# SCH_PCB_-_project_2022-06-17.net
KiCad netlist of a schematic drawn in EasyEDA
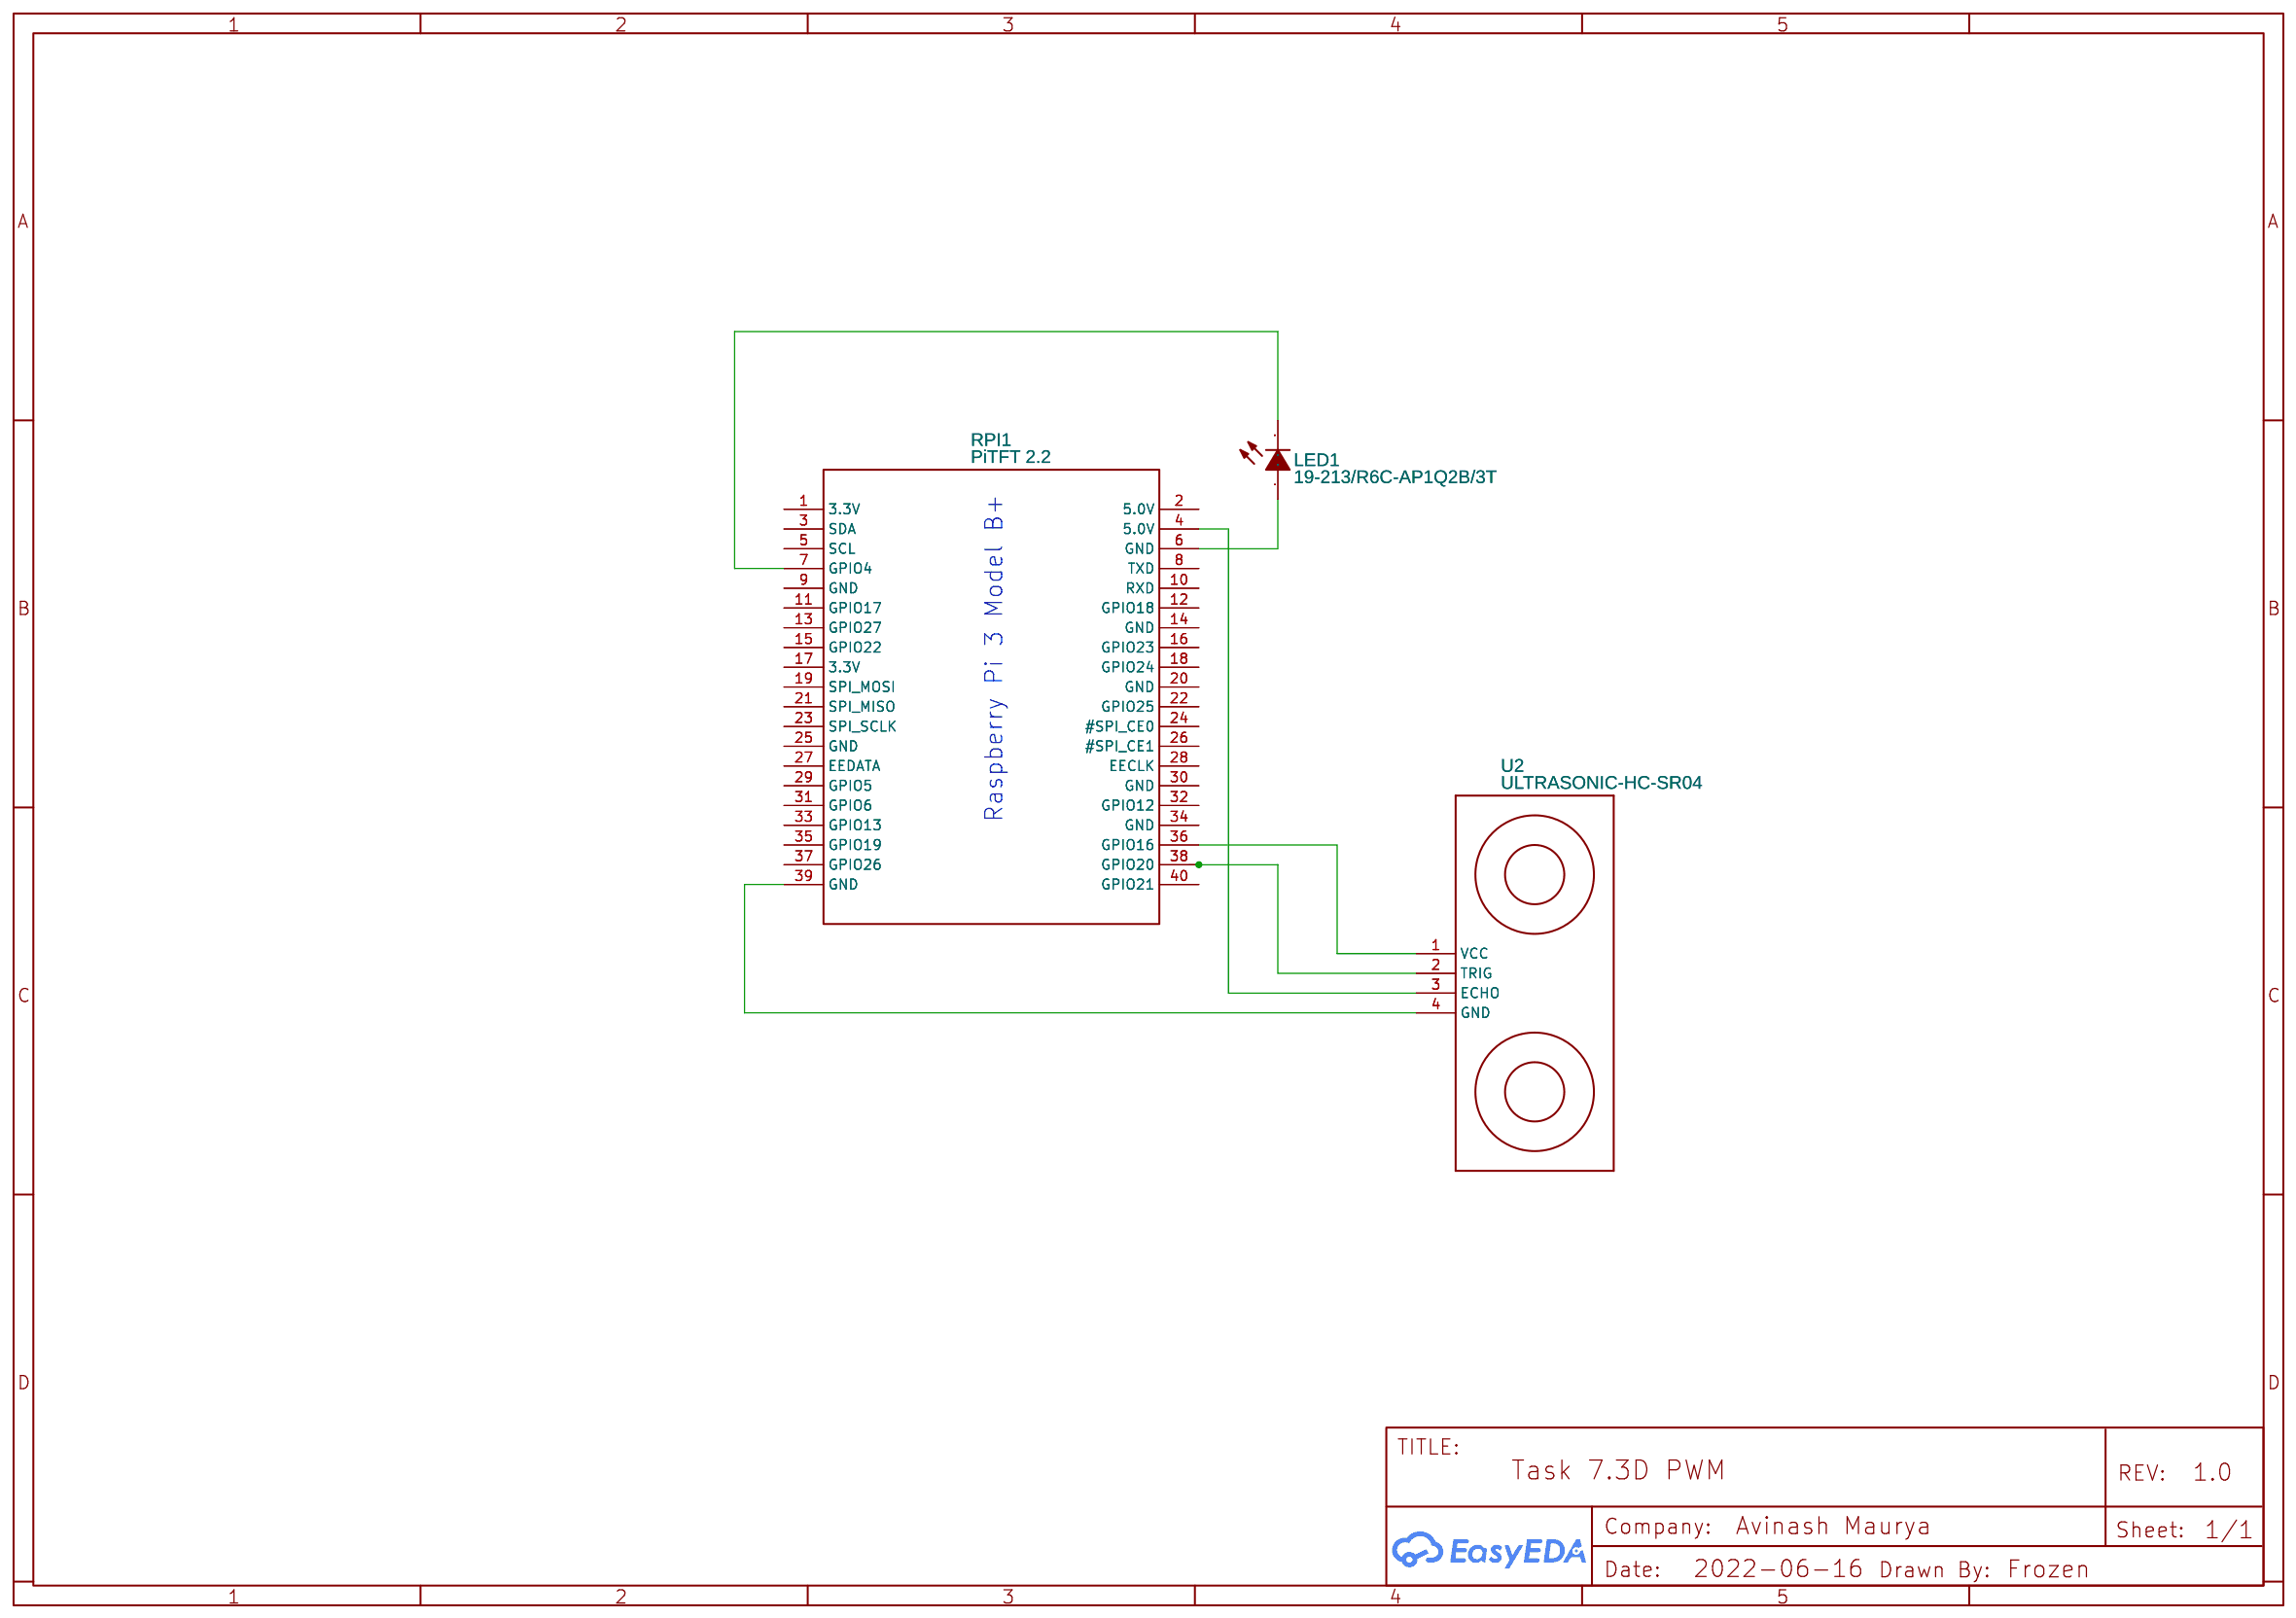
[diagram p0: Sheet_1]
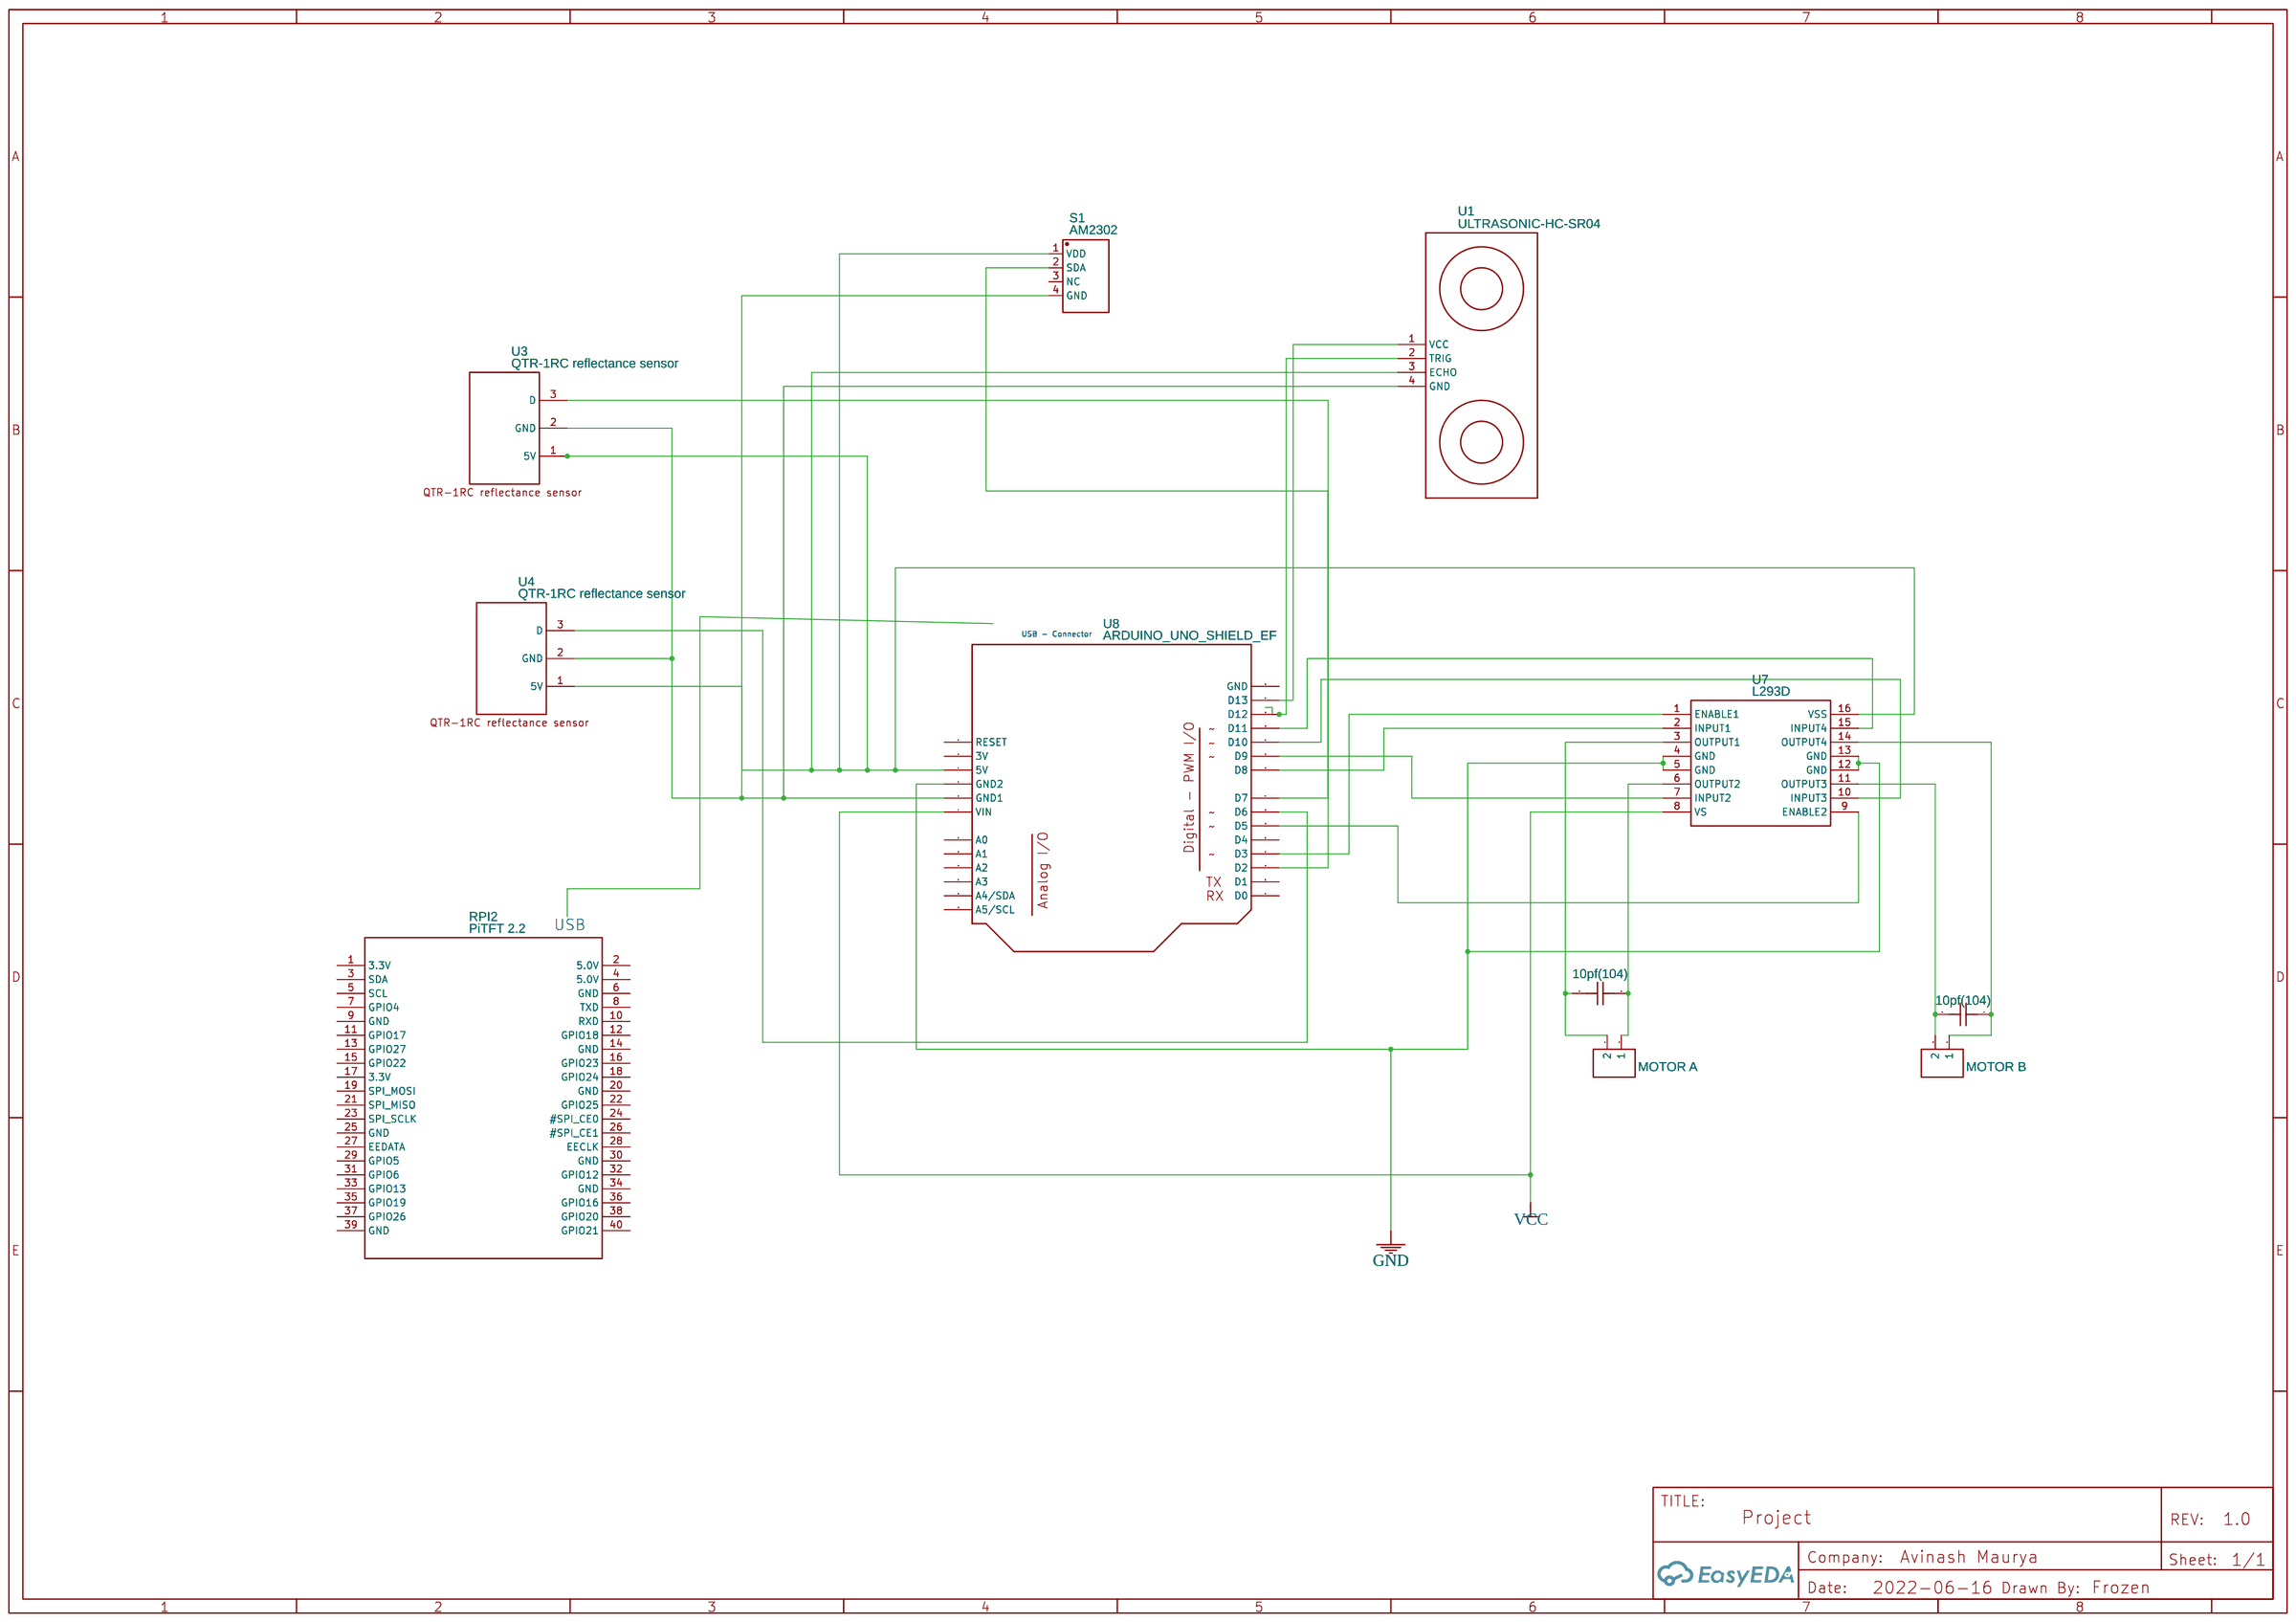
[diagram p1: Sheet_2]

(export (version "E")
  (design (tool "Eeschema 10.0.6"))
  (components
    (comp (ref "LED1")
      (value "19-213/R6C-AP1Q2B/3T")
      (fields (field (name "BOM_Supplier Part") "C212335"))
      (libsource (lib "") (part "19-213/R6C-AP1Q2B/3T"))
    )
    (comp (ref "RPI1") (value "PiTFT 2.2") (libsource (lib "") (part "PiTFT 2.2")))
    (comp (ref "U2") (value "ULTRASONIC-HC-SR04") (libsource (lib "") (part "ULTRASONIC-HC-SR04")))
    (comp (ref "C1") (value "10pf(104)") (libsource (lib "") (part "Cap_RAD-0.1_US")))
    (comp (ref "C2") (value "10pf(104)") (libsource (lib "") (part "Cap_RAD-0.1_US_1")))
    (comp (ref "P2")
      (value "MOTOR A")
      (fields
        (field (name "BOM_Manufacturer Part") "2.54-1*2PFemale")
        (field (name "BOM_Supplier Part") "C49661")
      )
      (libsource (lib "") (part "Unknown_1870_1395"))
    )
    (comp (ref "P3")
      (value "MOTOR B")
      (fields
        (field (name "BOM_Manufacturer Part") "2.54-1*2PFemale")
        (field (name "BOM_Supplier Part") "C49661")
      )
      (libsource (lib "") (part "Unknown_2105_1395"))
    )
    (comp (ref "RPI2") (value "PiTFT 2.2") (libsource (lib "") (part "PiTFT 2.2")))
    (comp (ref "S1")
      (value "AM2302")
      (fields (field (name "BOM_Supplier Part") "C83988"))
      (libsource (lib "") (part "AM2302"))
    )
    (comp (ref "U1") (value "ULTRASONIC-HC-SR04") (libsource (lib "") (part "ULTRASONIC-HC-SR04")))
    (comp (ref "U3")
      (value "QTR-1RC reflectance sensor")
      (libsource (lib "") (part "QTR-1RC reflectance sensor"))
    )
    (comp (ref "U4")
      (value "QTR-1RC reflectance sensor")
      (libsource (lib "") (part "QTR-1RC reflectance sensor"))
    )
    (comp (ref "U7")
      (value "L293D")
      (fields (field (name "BOM_Supplier Part") "C12340"))
      (libsource (lib "") (part "Unknown_1975_1190"))
    )
    (comp (ref "U8")
      (value "ARDUINO_UNO_SHIELD_EF")
      (fields (field (name "BOM_Manufacturer Part") "Arduino_UNO_R3_Shield"))
      (libsource (lib "") (part "Unknown_1510_1190"))
    )
  )
  (nets
    (net (code "1") (name "GND") (class "Default")
      (node (ref "U7") (pin "12") (pinfunction "GND_12") (pintype "unspecified"))
      (node (ref "U7") (pin "13") (pinfunction "GND_13") (pintype "unspecified"))
      (node (ref "U7") (pin "4") (pinfunction "GND_4") (pintype "unspecified"))
      (node (ref "U7") (pin "5") (pinfunction "GND_5") (pintype "unspecified"))
      (node (ref "U8") (pin "5") (pinfunction "GND2_5") (pintype "passive"))
    )
    (net (code "2") (name "Net-(LED1-A)") (class "Default")
      (node (ref "LED1") (pin "1") (pinfunction "A_1") (pintype "input"))
      (node (ref "RPI1") (pin "6") (pinfunction "GND_6") (pintype "unspecified"))
    )
    (net (code "3") (name "Net-(LED1-C)") (class "Default")
      (node (ref "LED1") (pin "2") (pinfunction "C_2") (pintype "input"))
      (node (ref "RPI1") (pin "7") (pinfunction "GPIO4_7") (pintype "unspecified"))
    )
    (net (code "4") (name "Net-(RPI1-GPIO16)") (class "Default")
      (node (ref "RPI1") (pin "36") (pinfunction "GPIO16_36") (pintype "unspecified"))
      (node (ref "U2") (pin "1") (pinfunction "VCC_1") (pintype "passive"))
    )
    (net (code "5") (name "Net-(RPI1-GPIO20)") (class "Default")
      (node (ref "RPI1") (pin "38") (pinfunction "GPIO20_38") (pintype "unspecified"))
      (node (ref "U2") (pin "2") (pinfunction "TRIG_2") (pintype "input"))
    )
    (net (code "6") (name "Net-(S1-GND)") (class "Default")
      (node (ref "S1") (pin "4") (pinfunction "GND_4") (pintype "unspecified"))
      (node (ref "U1") (pin "4") (pinfunction "GND_4") (pintype "passive"))
      (node (ref "U3") (pin "2") (pinfunction "GND_2") (pintype "unspecified"))
      (node (ref "U4") (pin "2") (pinfunction "GND_2") (pintype "unspecified"))
      (node (ref "U8") (pin "6") (pinfunction "GND1_6") (pintype "passive"))
    )
    (net (code "7") (name "Net-(S1-SDA)") (class "Default")
      (node (ref "S1") (pin "2") (pinfunction "SDA_2") (pintype "unspecified"))
      (node (ref "U8") (pin "16") (pinfunction "D2_16") (pintype "unspecified"))
    )
    (net (code "8") (name "Net-(S1-VDD)") (class "Default")
      (node (ref "S1") (pin "1") (pinfunction "VDD_1") (pintype "unspecified"))
      (node (ref "U1") (pin "3") (pinfunction "ECHO_3") (pintype "output"))
      (node (ref "U3") (pin "1") (pinfunction "5V_1") (pintype "unspecified"))
      (node (ref "U4") (pin "1") (pinfunction "5V_1") (pintype "unspecified"))
      (node (ref "U7") (pin "16") (pinfunction "VSS_16") (pintype "unspecified"))
      (node (ref "U8") (pin "4") (pinfunction "5V_4") (pintype "passive"))
    )
    (net (code "9") (name "Net-(U1-TRIG)") (class "Default")
      (node (ref "U1") (pin "2") (pinfunction "TRIG_2") (pintype "input"))
      (node (ref "U8") (pin "26") (pinfunction "D12_26") (pintype "unspecified"))
    )
    (net (code "10") (name "Net-(U1-VCC)") (class "Default")
      (node (ref "U1") (pin "1") (pinfunction "VCC_1") (pintype "passive"))
      (node (ref "U8") (pin "27") (pinfunction "D13_27") (pintype "unspecified"))
    )
    (net (code "11") (name "Net-(U2-ECHO)") (class "Default")
      (node (ref "RPI1") (pin "4") (pinfunction "5.0V_4") (pintype "unspecified"))
      (node (ref "U2") (pin "3") (pinfunction "ECHO_3") (pintype "output"))
    )
    (net (code "12") (name "Net-(U2-GND)") (class "Default")
      (node (ref "RPI1") (pin "39") (pinfunction "GND_39") (pintype "unspecified"))
      (node (ref "U2") (pin "4") (pinfunction "GND_4") (pintype "passive"))
    )
    (net (code "13") (name "Net-(U3-D)") (class "Default")
      (node (ref "U3") (pin "3") (pinfunction "D_3") (pintype "unspecified"))
      (node (ref "U8") (pin "21") (pinfunction "D7_21") (pintype "unspecified"))
    )
    (net (code "14") (name "Net-(U4-D)") (class "Default")
      (node (ref "U4") (pin "3") (pinfunction "D_3") (pintype "unspecified"))
      (node (ref "U8") (pin "20") (pinfunction "D6_20") (pintype "unspecified"))
    )
    (net (code "15") (name "Net-(U7-ENABLE1)") (class "Default")
      (node (ref "U7") (pin "1") (pinfunction "ENABLE1_1") (pintype "unspecified"))
      (node (ref "U8") (pin "17") (pinfunction "D3_17") (pintype "unspecified"))
    )
    (net (code "16") (name "Net-(U7-ENABLE2)") (class "Default")
      (node (ref "U7") (pin "9") (pinfunction "ENABLE2_9") (pintype "unspecified"))
      (node (ref "U8") (pin "19") (pinfunction "D5_19") (pintype "unspecified"))
    )
    (net (code "17") (name "Net-(U7-INPUT1)") (class "Default")
      (node (ref "U7") (pin "2") (pinfunction "INPUT1_2") (pintype "unspecified"))
      (node (ref "U8") (pin "22") (pinfunction "D8_22") (pintype "unspecified"))
    )
    (net (code "18") (name "Net-(U7-INPUT2)") (class "Default")
      (node (ref "U7") (pin "7") (pinfunction "INPUT2_7") (pintype "unspecified"))
      (node (ref "U8") (pin "23") (pinfunction "D9_23") (pintype "unspecified"))
    )
    (net (code "19") (name "Net-(U7-INPUT3)") (class "Default")
      (node (ref "U7") (pin "10") (pinfunction "INPUT3_10") (pintype "unspecified"))
      (node (ref "U8") (pin "24") (pinfunction "D10_24") (pintype "unspecified"))
    )
    (net (code "20") (name "Net-(U7-INPUT4)") (class "Default")
      (node (ref "U7") (pin "15") (pinfunction "INPUT4_15") (pintype "unspecified"))
      (node (ref "U8") (pin "25") (pinfunction "D11_25") (pintype "unspecified"))
    )
    (net (code "21") (name "Net-(U7-OUTPUT1)") (class "Default")
      (node (ref "C2") (pin "1") (pinfunction "1_1") (pintype "unspecified"))
      (node (ref "P2") (pin "2") (pinfunction "2_2") (pintype "input"))
      (node (ref "U7") (pin "3") (pinfunction "OUTPUT1_3") (pintype "unspecified"))
    )
    (net (code "22") (name "Net-(U7-OUTPUT2)") (class "Default")
      (node (ref "C2") (pin "2") (pinfunction "2_2") (pintype "unspecified"))
      (node (ref "P2") (pin "1") (pinfunction "1_1") (pintype "input"))
      (node (ref "U7") (pin "6") (pinfunction "OUTPUT2_6") (pintype "unspecified"))
    )
    (net (code "23") (name "Net-(U7-OUTPUT3)") (class "Default")
      (node (ref "C1") (pin "2") (pinfunction "2_2") (pintype "unspecified"))
      (node (ref "P3") (pin "2") (pinfunction "2_2") (pintype "input"))
      (node (ref "U7") (pin "11") (pinfunction "OUTPUT3_11") (pintype "unspecified"))
    )
    (net (code "24") (name "Net-(U7-OUTPUT4)") (class "Default")
      (node (ref "C1") (pin "1") (pinfunction "1_1") (pintype "unspecified"))
      (node (ref "P3") (pin "1") (pinfunction "1_1") (pintype "input"))
      (node (ref "U7") (pin "14") (pinfunction "OUTPUT4_14") (pintype "unspecified"))
    )
    (net (code "25") (name "VCC") (class "Default")
      (node (ref "U7") (pin "8") (pinfunction "VS_8") (pintype "unspecified"))
      (node (ref "U8") (pin "7") (pinfunction "VIN_7") (pintype "passive"))
    )
    (net (code "26") (name "unconnected-(RPI1-#SPI_CE0-Pad24)") (class "Default")
      (node (ref "RPI1") (pin "24") (pinfunction "#SPI_CE0_24") (pintype "unspecified"))
    )
    (net (code "27") (name "unconnected-(RPI1-#SPI_CE1-Pad26)") (class "Default")
      (node (ref "RPI1") (pin "26") (pinfunction "#SPI_CE1_26") (pintype "unspecified"))
    )
    (net (code "28") (name "unconnected-(RPI1-3.3V-Pad1)") (class "Default")
      (node (ref "RPI1") (pin "1") (pinfunction "3.3V_1") (pintype "unspecified"))
    )
    (net (code "29") (name "unconnected-(RPI1-3.3V-Pad17)") (class "Default")
      (node (ref "RPI1") (pin "17") (pinfunction "3.3V_17") (pintype "unspecified"))
    )
    (net (code "30") (name "unconnected-(RPI1-5.0V-Pad2)") (class "Default")
      (node (ref "RPI1") (pin "2") (pinfunction "5.0V_2") (pintype "unspecified"))
    )
    (net (code "31") (name "unconnected-(RPI1-EECLK-Pad28)") (class "Default")
      (node (ref "RPI1") (pin "28") (pinfunction "EECLK_28") (pintype "unspecified"))
    )
    (net (code "32") (name "unconnected-(RPI1-EEDATA-Pad27)") (class "Default")
      (node (ref "RPI1") (pin "27") (pinfunction "EEDATA_27") (pintype "unspecified"))
    )
    (net (code "33") (name "unconnected-(RPI1-GND-Pad9)") (class "Default")
      (node (ref "RPI1") (pin "9") (pinfunction "GND_9") (pintype "unspecified"))
    )
    (net (code "34") (name "unconnected-(RPI1-GND-Pad14)") (class "Default")
      (node (ref "RPI1") (pin "14") (pinfunction "GND_14") (pintype "unspecified"))
    )
    (net (code "35") (name "unconnected-(RPI1-GND-Pad20)") (class "Default")
      (node (ref "RPI1") (pin "20") (pinfunction "GND_20") (pintype "unspecified"))
    )
    (net (code "36") (name "unconnected-(RPI1-GND-Pad25)") (class "Default")
      (node (ref "RPI1") (pin "25") (pinfunction "GND_25") (pintype "unspecified"))
    )
    (net (code "37") (name "unconnected-(RPI1-GND-Pad30)") (class "Default")
      (node (ref "RPI1") (pin "30") (pinfunction "GND_30") (pintype "unspecified"))
    )
    (net (code "38") (name "unconnected-(RPI1-GND-Pad34)") (class "Default")
      (node (ref "RPI1") (pin "34") (pinfunction "GND_34") (pintype "unspecified"))
    )
    (net (code "39") (name "unconnected-(RPI1-GPIO5-Pad29)") (class "Default")
      (node (ref "RPI1") (pin "29") (pinfunction "GPIO5_29") (pintype "unspecified"))
    )
    (net (code "40") (name "unconnected-(RPI1-GPIO6-Pad31)") (class "Default")
      (node (ref "RPI1") (pin "31") (pinfunction "GPIO6_31") (pintype "unspecified"))
    )
    (net (code "41") (name "unconnected-(RPI1-GPIO12-Pad32)") (class "Default")
      (node (ref "RPI1") (pin "32") (pinfunction "GPIO12_32") (pintype "unspecified"))
    )
    (net (code "42") (name "unconnected-(RPI1-GPIO13-Pad33)") (class "Default")
      (node (ref "RPI1") (pin "33") (pinfunction "GPIO13_33") (pintype "unspecified"))
    )
    (net (code "43") (name "unconnected-(RPI1-GPIO17-Pad11)") (class "Default")
      (node (ref "RPI1") (pin "11") (pinfunction "GPIO17_11") (pintype "unspecified"))
    )
    (net (code "44") (name "unconnected-(RPI1-GPIO18-Pad12)") (class "Default")
      (node (ref "RPI1") (pin "12") (pinfunction "GPIO18_12") (pintype "unspecified"))
    )
    (net (code "45") (name "unconnected-(RPI1-GPIO19-Pad35)") (class "Default")
      (node (ref "RPI1") (pin "35") (pinfunction "GPIO19_35") (pintype "unspecified"))
    )
    (net (code "46") (name "unconnected-(RPI1-GPIO21-Pad40)") (class "Default")
      (node (ref "RPI1") (pin "40") (pinfunction "GPIO21_40") (pintype "unspecified"))
    )
    (net (code "47") (name "unconnected-(RPI1-GPIO22-Pad15)") (class "Default")
      (node (ref "RPI1") (pin "15") (pinfunction "GPIO22_15") (pintype "unspecified"))
    )
    (net (code "48") (name "unconnected-(RPI1-GPIO23-Pad16)") (class "Default")
      (node (ref "RPI1") (pin "16") (pinfunction "GPIO23_16") (pintype "unspecified"))
    )
    (net (code "49") (name "unconnected-(RPI1-GPIO24-Pad18)") (class "Default")
      (node (ref "RPI1") (pin "18") (pinfunction "GPIO24_18") (pintype "unspecified"))
    )
    (net (code "50") (name "unconnected-(RPI1-GPIO25-Pad22)") (class "Default")
      (node (ref "RPI1") (pin "22") (pinfunction "GPIO25_22") (pintype "unspecified"))
    )
    (net (code "51") (name "unconnected-(RPI1-GPIO26-Pad37)") (class "Default")
      (node (ref "RPI1") (pin "37") (pinfunction "GPIO26_37") (pintype "unspecified"))
    )
    (net (code "52") (name "unconnected-(RPI1-GPIO27-Pad13)") (class "Default")
      (node (ref "RPI1") (pin "13") (pinfunction "GPIO27_13") (pintype "unspecified"))
    )
    (net (code "53") (name "unconnected-(RPI1-RXD-Pad10)") (class "Default")
      (node (ref "RPI1") (pin "10") (pinfunction "RXD_10") (pintype "unspecified"))
    )
    (net (code "54") (name "unconnected-(RPI1-SCL-Pad5)") (class "Default")
      (node (ref "RPI1") (pin "5") (pinfunction "SCL_5") (pintype "unspecified"))
    )
    (net (code "55") (name "unconnected-(RPI1-SDA-Pad3)") (class "Default")
      (node (ref "RPI1") (pin "3") (pinfunction "SDA_3") (pintype "unspecified"))
    )
    (net (code "56") (name "unconnected-(RPI1-SPI_MISO-Pad21)") (class "Default")
      (node (ref "RPI1") (pin "21") (pinfunction "SPI_MISO_21") (pintype "unspecified"))
    )
    (net (code "57") (name "unconnected-(RPI1-SPI_MOSI-Pad19)") (class "Default")
      (node (ref "RPI1") (pin "19") (pinfunction "SPI_MOSI_19") (pintype "unspecified"))
    )
    (net (code "58") (name "unconnected-(RPI1-SPI_SCLK-Pad23)") (class "Default")
      (node (ref "RPI1") (pin "23") (pinfunction "SPI_SCLK_23") (pintype "unspecified"))
    )
    (net (code "59") (name "unconnected-(RPI1-TXD-Pad8)") (class "Default")
      (node (ref "RPI1") (pin "8") (pinfunction "TXD_8") (pintype "output"))
    )
    (net (code "60") (name "unconnected-(RPI2-#SPI_CE0-Pad24)") (class "Default")
      (node (ref "RPI2") (pin "24") (pinfunction "#SPI_CE0_24") (pintype "unspecified"))
    )
    (net (code "61") (name "unconnected-(RPI2-#SPI_CE1-Pad26)") (class "Default")
      (node (ref "RPI2") (pin "26") (pinfunction "#SPI_CE1_26") (pintype "unspecified"))
    )
    (net (code "62") (name "unconnected-(RPI2-3.3V-Pad1)") (class "Default")
      (node (ref "RPI2") (pin "1") (pinfunction "3.3V_1") (pintype "unspecified"))
    )
    (net (code "63") (name "unconnected-(RPI2-3.3V-Pad17)") (class "Default")
      (node (ref "RPI2") (pin "17") (pinfunction "3.3V_17") (pintype "unspecified"))
    )
    (net (code "64") (name "unconnected-(RPI2-5.0V-Pad2)") (class "Default")
      (node (ref "RPI2") (pin "2") (pinfunction "5.0V_2") (pintype "unspecified"))
    )
    (net (code "65") (name "unconnected-(RPI2-5.0V-Pad4)") (class "Default")
      (node (ref "RPI2") (pin "4") (pinfunction "5.0V_4") (pintype "unspecified"))
    )
    (net (code "66") (name "unconnected-(RPI2-EECLK-Pad28)") (class "Default")
      (node (ref "RPI2") (pin "28") (pinfunction "EECLK_28") (pintype "unspecified"))
    )
    (net (code "67") (name "unconnected-(RPI2-EEDATA-Pad27)") (class "Default")
      (node (ref "RPI2") (pin "27") (pinfunction "EEDATA_27") (pintype "unspecified"))
    )
    (net (code "68") (name "unconnected-(RPI2-GND-Pad6)") (class "Default")
      (node (ref "RPI2") (pin "6") (pinfunction "GND_6") (pintype "unspecified"))
    )
    (net (code "69") (name "unconnected-(RPI2-GND-Pad9)") (class "Default")
      (node (ref "RPI2") (pin "9") (pinfunction "GND_9") (pintype "unspecified"))
    )
    (net (code "70") (name "unconnected-(RPI2-GND-Pad14)") (class "Default")
      (node (ref "RPI2") (pin "14") (pinfunction "GND_14") (pintype "unspecified"))
    )
    (net (code "71") (name "unconnected-(RPI2-GND-Pad20)") (class "Default")
      (node (ref "RPI2") (pin "20") (pinfunction "GND_20") (pintype "unspecified"))
    )
    (net (code "72") (name "unconnected-(RPI2-GND-Pad25)") (class "Default")
      (node (ref "RPI2") (pin "25") (pinfunction "GND_25") (pintype "unspecified"))
    )
    (net (code "73") (name "unconnected-(RPI2-GND-Pad30)") (class "Default")
      (node (ref "RPI2") (pin "30") (pinfunction "GND_30") (pintype "unspecified"))
    )
    (net (code "74") (name "unconnected-(RPI2-GND-Pad34)") (class "Default")
      (node (ref "RPI2") (pin "34") (pinfunction "GND_34") (pintype "unspecified"))
    )
    (net (code "75") (name "unconnected-(RPI2-GND-Pad39)") (class "Default")
      (node (ref "RPI2") (pin "39") (pinfunction "GND_39") (pintype "unspecified"))
    )
    (net (code "76") (name "unconnected-(RPI2-GPIO4-Pad7)") (class "Default")
      (node (ref "RPI2") (pin "7") (pinfunction "GPIO4_7") (pintype "unspecified"))
    )
    (net (code "77") (name "unconnected-(RPI2-GPIO5-Pad29)") (class "Default")
      (node (ref "RPI2") (pin "29") (pinfunction "GPIO5_29") (pintype "unspecified"))
    )
    (net (code "78") (name "unconnected-(RPI2-GPIO6-Pad31)") (class "Default")
      (node (ref "RPI2") (pin "31") (pinfunction "GPIO6_31") (pintype "unspecified"))
    )
    (net (code "79") (name "unconnected-(RPI2-GPIO12-Pad32)") (class "Default")
      (node (ref "RPI2") (pin "32") (pinfunction "GPIO12_32") (pintype "unspecified"))
    )
    (net (code "80") (name "unconnected-(RPI2-GPIO13-Pad33)") (class "Default")
      (node (ref "RPI2") (pin "33") (pinfunction "GPIO13_33") (pintype "unspecified"))
    )
    (net (code "81") (name "unconnected-(RPI2-GPIO16-Pad36)") (class "Default")
      (node (ref "RPI2") (pin "36") (pinfunction "GPIO16_36") (pintype "unspecified"))
    )
    (net (code "82") (name "unconnected-(RPI2-GPIO17-Pad11)") (class "Default")
      (node (ref "RPI2") (pin "11") (pinfunction "GPIO17_11") (pintype "unspecified"))
    )
    (net (code "83") (name "unconnected-(RPI2-GPIO18-Pad12)") (class "Default")
      (node (ref "RPI2") (pin "12") (pinfunction "GPIO18_12") (pintype "unspecified"))
    )
    (net (code "84") (name "unconnected-(RPI2-GPIO19-Pad35)") (class "Default")
      (node (ref "RPI2") (pin "35") (pinfunction "GPIO19_35") (pintype "unspecified"))
    )
    (net (code "85") (name "unconnected-(RPI2-GPIO20-Pad38)") (class "Default")
      (node (ref "RPI2") (pin "38") (pinfunction "GPIO20_38") (pintype "unspecified"))
    )
    (net (code "86") (name "unconnected-(RPI2-GPIO21-Pad40)") (class "Default")
      (node (ref "RPI2") (pin "40") (pinfunction "GPIO21_40") (pintype "unspecified"))
    )
    (net (code "87") (name "unconnected-(RPI2-GPIO22-Pad15)") (class "Default")
      (node (ref "RPI2") (pin "15") (pinfunction "GPIO22_15") (pintype "unspecified"))
    )
    (net (code "88") (name "unconnected-(RPI2-GPIO23-Pad16)") (class "Default")
      (node (ref "RPI2") (pin "16") (pinfunction "GPIO23_16") (pintype "unspecified"))
    )
    (net (code "89") (name "unconnected-(RPI2-GPIO24-Pad18)") (class "Default")
      (node (ref "RPI2") (pin "18") (pinfunction "GPIO24_18") (pintype "unspecified"))
    )
    (net (code "90") (name "unconnected-(RPI2-GPIO25-Pad22)") (class "Default")
      (node (ref "RPI2") (pin "22") (pinfunction "GPIO25_22") (pintype "unspecified"))
    )
    (net (code "91") (name "unconnected-(RPI2-GPIO26-Pad37)") (class "Default")
      (node (ref "RPI2") (pin "37") (pinfunction "GPIO26_37") (pintype "unspecified"))
    )
    (net (code "92") (name "unconnected-(RPI2-GPIO27-Pad13)") (class "Default")
      (node (ref "RPI2") (pin "13") (pinfunction "GPIO27_13") (pintype "unspecified"))
    )
    (net (code "93") (name "unconnected-(RPI2-RXD-Pad10)") (class "Default")
      (node (ref "RPI2") (pin "10") (pinfunction "RXD_10") (pintype "unspecified"))
    )
    (net (code "94") (name "unconnected-(RPI2-SCL-Pad5)") (class "Default")
      (node (ref "RPI2") (pin "5") (pinfunction "SCL_5") (pintype "unspecified"))
    )
    (net (code "95") (name "unconnected-(RPI2-SDA-Pad3)") (class "Default")
      (node (ref "RPI2") (pin "3") (pinfunction "SDA_3") (pintype "unspecified"))
    )
    (net (code "96") (name "unconnected-(RPI2-SPI_MISO-Pad21)") (class "Default")
      (node (ref "RPI2") (pin "21") (pinfunction "SPI_MISO_21") (pintype "unspecified"))
    )
    (net (code "97") (name "unconnected-(RPI2-SPI_MOSI-Pad19)") (class "Default")
      (node (ref "RPI2") (pin "19") (pinfunction "SPI_MOSI_19") (pintype "unspecified"))
    )
    (net (code "98") (name "unconnected-(RPI2-SPI_SCLK-Pad23)") (class "Default")
      (node (ref "RPI2") (pin "23") (pinfunction "SPI_SCLK_23") (pintype "unspecified"))
    )
    (net (code "99") (name "unconnected-(RPI2-TXD-Pad8)") (class "Default")
      (node (ref "RPI2") (pin "8") (pinfunction "TXD_8") (pintype "output"))
    )
    (net (code "100") (name "unconnected-(S1-NC-Pad3)") (class "Default")
      (node (ref "S1") (pin "3") (pinfunction "NC_3") (pintype "unspecified"))
    )
    (net (code "101") (name "unconnected-(U8-3V-Pad3)") (class "Default")
      (node (ref "U8") (pin "3") (pinfunction "3V_3") (pintype "passive"))
    )
    (net (code "102") (name "unconnected-(U8-A0-Pad8)") (class "Default")
      (node (ref "U8") (pin "8") (pinfunction "A0_8") (pintype "unspecified"))
    )
    (net (code "103") (name "unconnected-(U8-A1-Pad9)") (class "Default")
      (node (ref "U8") (pin "9") (pinfunction "A1_9") (pintype "unspecified"))
    )
    (net (code "104") (name "unconnected-(U8-A2-Pad10)") (class "Default")
      (node (ref "U8") (pin "10") (pinfunction "A2_10") (pintype "unspecified"))
    )
    (net (code "105") (name "unconnected-(U8-A3-Pad11)") (class "Default")
      (node (ref "U8") (pin "11") (pinfunction "A3_11") (pintype "unspecified"))
    )
    (net (code "106") (name "unconnected-(U8-A4{slash}SDA-Pad12)") (class "Default")
      (node (ref "U8") (pin "12") (pinfunction "A4/SDA_12") (pintype "unspecified"))
    )
    (net (code "107") (name "unconnected-(U8-A5{slash}SCL-Pad13)") (class "Default")
      (node (ref "U8") (pin "13") (pinfunction "A5/SCL_13") (pintype "unspecified"))
    )
    (net (code "108") (name "unconnected-(U8-D0-Pad14)") (class "Default")
      (node (ref "U8") (pin "14") (pinfunction "D0_14") (pintype "unspecified"))
    )
    (net (code "109") (name "unconnected-(U8-D1-Pad15)") (class "Default")
      (node (ref "U8") (pin "15") (pinfunction "D1_15") (pintype "unspecified"))
    )
    (net (code "110") (name "unconnected-(U8-D4-Pad18)") (class "Default")
      (node (ref "U8") (pin "18") (pinfunction "D4_18") (pintype "unspecified"))
    )
    (net (code "111") (name "unconnected-(U8-GND-Pad28)") (class "Default")
      (node (ref "U8") (pin "28") (pinfunction "GND_28") (pintype "passive"))
    )
    (net (code "112") (name "unconnected-(U8-RESET-Pad2)") (class "Default")
      (node (ref "U8") (pin "2") (pinfunction "RESET_2") (pintype "unspecified"))
    )
  )
)
